# MPU-6050_BreakoutV11.net
KiCad netlist of a schematic drawn in EAGLE
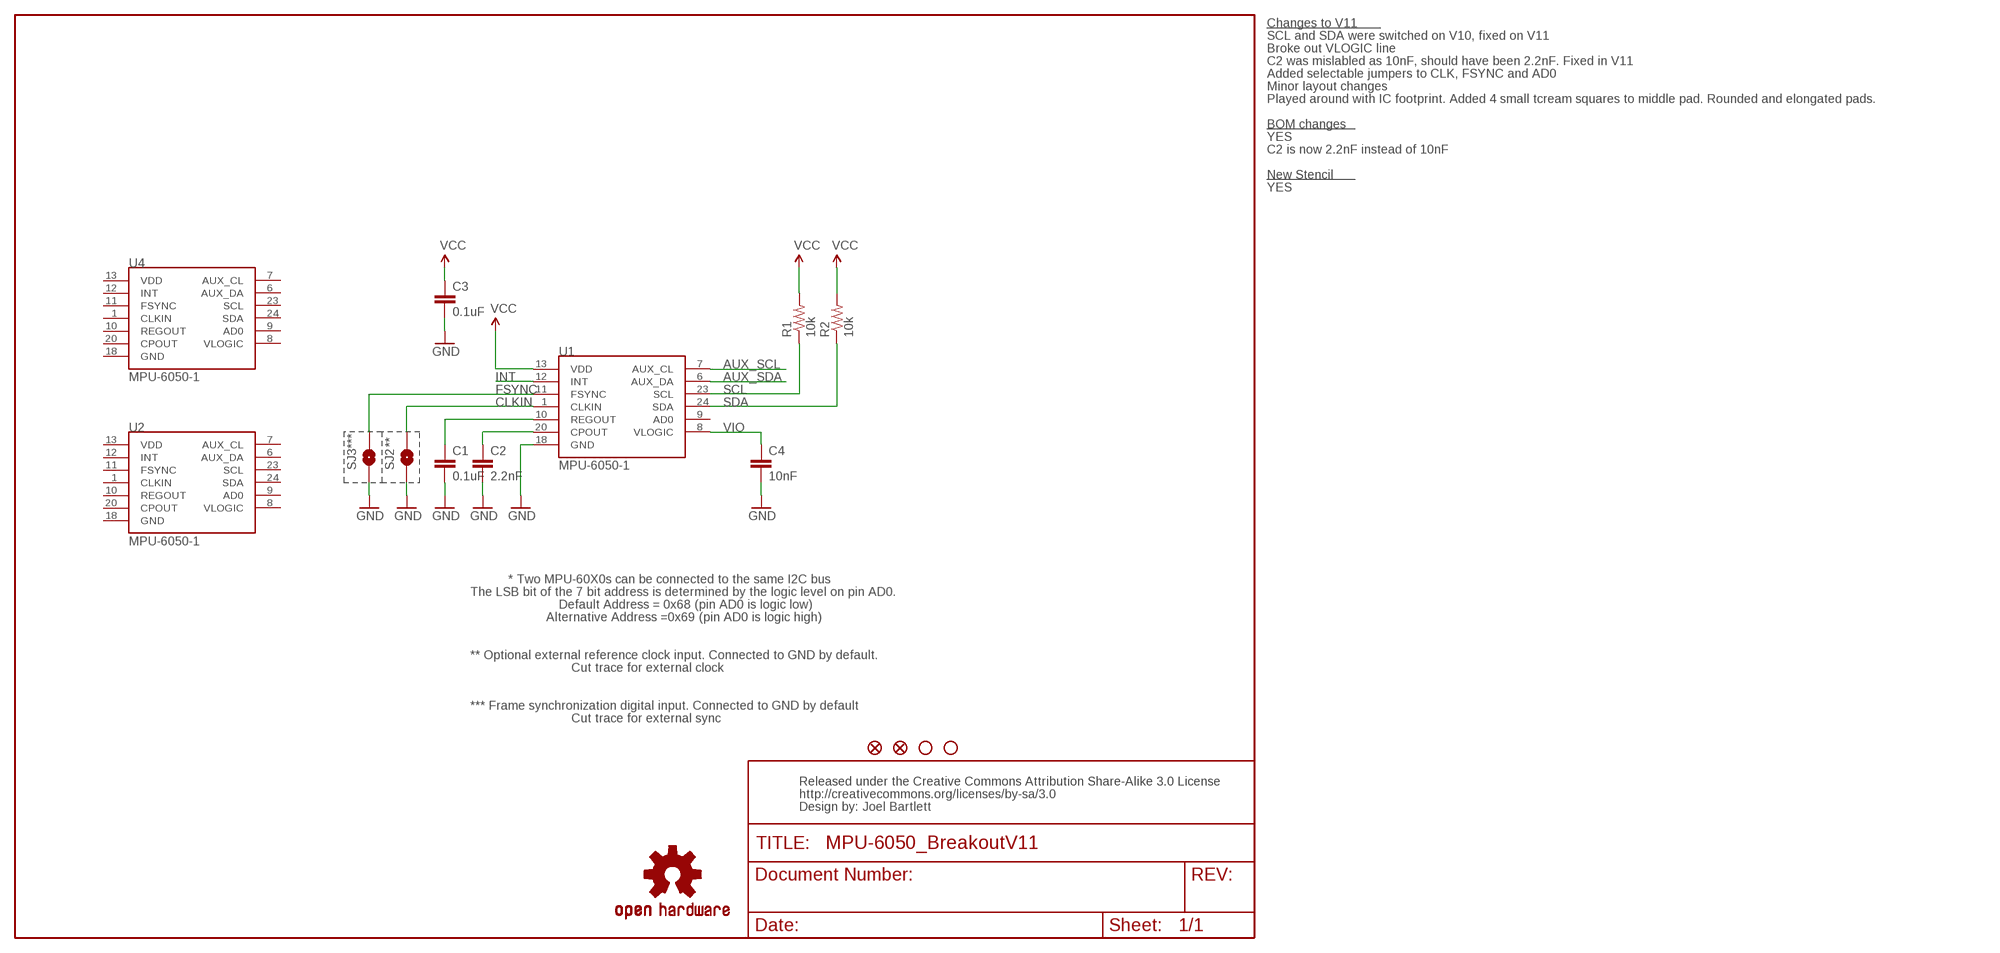
[diagram p0: schematic, sheet 1]

(export (version "E")
  (design (tool "Eeschema 10.0.6"))
  (components
    (comp (ref "C1")
      (value "0.1uF")
      (footprint "eagle-import:0402-CAP")
      (libsource (lib "eagle-import") (part "CAP0402-CAP"))
    )
    (comp (ref "C2")
      (value "2.2nF")
      (footprint "eagle-import:0402-CAP")
      (libsource (lib "eagle-import") (part "CAP0402-CAP"))
    )
    (comp (ref "C3")
      (value "0.1uF")
      (footprint "eagle-import:0402-CAP")
      (libsource (lib "eagle-import") (part "CAP0402-CAP"))
    )
    (comp (ref "C4")
      (value "10nF")
      (footprint "eagle-import:0402-CAP")
      (libsource (lib "eagle-import") (part "CAP0402-CAP"))
    )
    (comp (ref "JP2")
      (value "FIDUCIALUFIDUCIAL")
      (footprint "eagle-import:MICRO-FIDUCIAL")
      (libsource (lib "eagle-import") (part "FIDUCIALUFIDUCIAL"))
    )
    (comp (ref "JP3")
      (value "STAND-OFFTIGHT")
      (footprint "eagle-import:STAND-OFF-TIGHT")
      (libsource (lib "eagle-import") (part "STAND-OFFTIGHT"))
    )
    (comp (ref "JP4")
      (value "STAND-OFFTIGHT")
      (footprint "eagle-import:STAND-OFF-TIGHT")
      (libsource (lib "eagle-import") (part "STAND-OFFTIGHT"))
    )
    (comp (ref "JP5")
      (value "FIDUCIALUFIDUCIAL")
      (footprint "eagle-import:MICRO-FIDUCIAL")
      (libsource (lib "eagle-import") (part "FIDUCIALUFIDUCIAL"))
    )
    (comp (ref "R1")
      (value "10k")
      (footprint "eagle-import:0402-RES")
      (libsource (lib "eagle-import") (part "RESISTOR0402-RES"))
    )
    (comp (ref "R2")
      (value "10k")
      (footprint "eagle-import:0402-RES")
      (libsource (lib "eagle-import") (part "RESISTOR0402-RES"))
    )
    (comp (ref "SJ2")
      (value "SOLDERJUMPERTRACE")
      (footprint "eagle-import:SJ_2S-TRACE")
      (libsource (lib "eagle-import") (part "SOLDERJUMPERTRACE"))
    )
    (comp (ref "SJ3")
      (value "SOLDERJUMPERTRACE")
      (footprint "eagle-import:SJ_2S-TRACE")
      (libsource (lib "eagle-import") (part "SOLDERJUMPERTRACE"))
    )
    (comp (ref "U$1")
      (value "OSHW-LOGOS")
      (footprint "eagle-import:OSHW-LOGO-S")
      (libsource (lib "eagle-import") (part "OSHW-LOGOS"))
    )
    (comp (ref "U1")
      (value "MPU-6050-1")
      (footprint "eagle-import:QFN-24-4MM2")
      (libsource (lib "eagle-import") (part "MPU-6050-1"))
    )
    (comp (ref "U2")
      (value "MPU-6050-1")
      (footprint "eagle-import:QFN-24-4MM2")
      (libsource (lib "eagle-import") (part "MPU-6050-1"))
    )
    (comp (ref "U3")
      (value "CREATIVE_COMMONS")
      (footprint "eagle-import:CREATIVE_COMMONS")
      (libsource (lib "eagle-import") (part "CREATIVE_COMMONS"))
    )
    (comp (ref "U4")
      (value "MPU-6050-1")
      (footprint "eagle-import:QFN-24-4MM2")
      (libsource (lib "eagle-import") (part "MPU-6050-1"))
    )
  )
  (nets
    (net (code "1") (name "/AUX_SCL") (class "Default")
      (node (ref "U1") (pin "7") (pinfunction "AUX_CL_7") (pintype "bidirectional"))
    )
    (net (code "2") (name "/AUX_SDA") (class "Default")
      (node (ref "U1") (pin "6") (pinfunction "AUX_DA_6") (pintype "bidirectional"))
    )
    (net (code "3") (name "/CLKIN") (class "Default")
      (node (ref "SJ2") (pin "2") (pinfunction "2_2") (pintype "passive"))
      (node (ref "U1") (pin "1") (pinfunction "CLKIN_1") (pintype "bidirectional"))
    )
    (net (code "4") (name "/FSYNC") (class "Default")
      (node (ref "SJ3") (pin "2") (pinfunction "2_2") (pintype "passive"))
      (node (ref "U1") (pin "11") (pinfunction "FSYNC_11") (pintype "bidirectional"))
    )
    (net (code "5") (name "/INT") (class "Default")
      (node (ref "U1") (pin "12") (pinfunction "INT_12") (pintype "bidirectional"))
    )
    (net (code "6") (name "/SCL") (class "Default")
      (node (ref "R1") (pin "1") (pinfunction "1_1") (pintype "passive"))
      (node (ref "U1") (pin "23") (pinfunction "SCL_23") (pintype "bidirectional"))
    )
    (net (code "7") (name "/SDA") (class "Default")
      (node (ref "R2") (pin "1") (pinfunction "1_1") (pintype "passive"))
      (node (ref "U1") (pin "24") (pinfunction "SDA_24") (pintype "bidirectional"))
    )
    (net (code "8") (name "/VIO") (class "Default")
      (node (ref "C4") (pin "1") (pinfunction "1_1") (pintype "passive"))
      (node (ref "U1") (pin "8") (pinfunction "VLOGIC_8") (pintype "bidirectional"))
    )
    (net (code "9") (name "GND") (class "Default")
      (node (ref "C1") (pin "2") (pinfunction "2_2") (pintype "passive"))
      (node (ref "C2") (pin "2") (pinfunction "2_2") (pintype "passive"))
      (node (ref "C3") (pin "2") (pinfunction "2_2") (pintype "passive"))
      (node (ref "C4") (pin "2") (pinfunction "2_2") (pintype "passive"))
      (node (ref "SJ2") (pin "1") (pinfunction "1_1") (pintype "passive"))
      (node (ref "SJ3") (pin "1") (pinfunction "1_1") (pintype "passive"))
      (node (ref "U1") (pin "18") (pinfunction "GND_18") (pintype "bidirectional"))
    )
    (net (code "10") (name "Net-(U1-CPOUT)") (class "Default")
      (node (ref "C2") (pin "1") (pinfunction "1_1") (pintype "passive"))
      (node (ref "U1") (pin "20") (pinfunction "CPOUT_20") (pintype "bidirectional"))
    )
    (net (code "11") (name "Net-(U1-REGOUT)") (class "Default")
      (node (ref "C1") (pin "1") (pinfunction "1_1") (pintype "passive"))
      (node (ref "U1") (pin "10") (pinfunction "REGOUT_10") (pintype "bidirectional"))
    )
    (net (code "12") (name "VCC") (class "Default")
      (node (ref "C3") (pin "1") (pinfunction "1_1") (pintype "passive"))
      (node (ref "R1") (pin "2") (pinfunction "2_2") (pintype "passive"))
      (node (ref "R2") (pin "2") (pinfunction "2_2") (pintype "passive"))
      (node (ref "U1") (pin "13") (pinfunction "VDD_13") (pintype "bidirectional"))
    )
    (net (code "13") (name "unconnected-(U1-AD0-Pad9)") (class "Default")
      (node (ref "U1") (pin "9") (pinfunction "AD0_9") (pintype "bidirectional"))
    )
    (net (code "14") (name "unconnected-(U2-AD0-Pad9)") (class "Default")
      (node (ref "U2") (pin "9") (pinfunction "AD0_9") (pintype "bidirectional"))
    )
    (net (code "15") (name "unconnected-(U2-AUX_CL-Pad7)") (class "Default")
      (node (ref "U2") (pin "7") (pinfunction "AUX_CL_7") (pintype "bidirectional"))
    )
    (net (code "16") (name "unconnected-(U2-AUX_DA-Pad6)") (class "Default")
      (node (ref "U2") (pin "6") (pinfunction "AUX_DA_6") (pintype "bidirectional"))
    )
    (net (code "17") (name "unconnected-(U2-CLKIN-Pad1)") (class "Default")
      (node (ref "U2") (pin "1") (pinfunction "CLKIN_1") (pintype "bidirectional"))
    )
    (net (code "18") (name "unconnected-(U2-CPOUT-Pad20)") (class "Default")
      (node (ref "U2") (pin "20") (pinfunction "CPOUT_20") (pintype "bidirectional"))
    )
    (net (code "19") (name "unconnected-(U2-FSYNC-Pad11)") (class "Default")
      (node (ref "U2") (pin "11") (pinfunction "FSYNC_11") (pintype "bidirectional"))
    )
    (net (code "20") (name "unconnected-(U2-GND-Pad18)") (class "Default")
      (node (ref "U2") (pin "18") (pinfunction "GND_18") (pintype "bidirectional"))
    )
    (net (code "21") (name "unconnected-(U2-INT-Pad12)") (class "Default")
      (node (ref "U2") (pin "12") (pinfunction "INT_12") (pintype "bidirectional"))
    )
    (net (code "22") (name "unconnected-(U2-REGOUT-Pad10)") (class "Default")
      (node (ref "U2") (pin "10") (pinfunction "REGOUT_10") (pintype "bidirectional"))
    )
    (net (code "23") (name "unconnected-(U2-SCL-Pad23)") (class "Default")
      (node (ref "U2") (pin "23") (pinfunction "SCL_23") (pintype "bidirectional"))
    )
    (net (code "24") (name "unconnected-(U2-SDA-Pad24)") (class "Default")
      (node (ref "U2") (pin "24") (pinfunction "SDA_24") (pintype "bidirectional"))
    )
    (net (code "25") (name "unconnected-(U2-VDD-Pad13)") (class "Default")
      (node (ref "U2") (pin "13") (pinfunction "VDD_13") (pintype "bidirectional"))
    )
    (net (code "26") (name "unconnected-(U2-VLOGIC-Pad8)") (class "Default")
      (node (ref "U2") (pin "8") (pinfunction "VLOGIC_8") (pintype "bidirectional"))
    )
    (net (code "27") (name "unconnected-(U4-AD0-Pad9)") (class "Default")
      (node (ref "U4") (pin "9") (pinfunction "AD0_9") (pintype "bidirectional"))
    )
    (net (code "28") (name "unconnected-(U4-AUX_CL-Pad7)") (class "Default")
      (node (ref "U4") (pin "7") (pinfunction "AUX_CL_7") (pintype "bidirectional"))
    )
    (net (code "29") (name "unconnected-(U4-AUX_DA-Pad6)") (class "Default")
      (node (ref "U4") (pin "6") (pinfunction "AUX_DA_6") (pintype "bidirectional"))
    )
    (net (code "30") (name "unconnected-(U4-CLKIN-Pad1)") (class "Default")
      (node (ref "U4") (pin "1") (pinfunction "CLKIN_1") (pintype "bidirectional"))
    )
    (net (code "31") (name "unconnected-(U4-CPOUT-Pad20)") (class "Default")
      (node (ref "U4") (pin "20") (pinfunction "CPOUT_20") (pintype "bidirectional"))
    )
    (net (code "32") (name "unconnected-(U4-FSYNC-Pad11)") (class "Default")
      (node (ref "U4") (pin "11") (pinfunction "FSYNC_11") (pintype "bidirectional"))
    )
    (net (code "33") (name "unconnected-(U4-GND-Pad18)") (class "Default")
      (node (ref "U4") (pin "18") (pinfunction "GND_18") (pintype "bidirectional"))
    )
    (net (code "34") (name "unconnected-(U4-INT-Pad12)") (class "Default")
      (node (ref "U4") (pin "12") (pinfunction "INT_12") (pintype "bidirectional"))
    )
    (net (code "35") (name "unconnected-(U4-REGOUT-Pad10)") (class "Default")
      (node (ref "U4") (pin "10") (pinfunction "REGOUT_10") (pintype "bidirectional"))
    )
    (net (code "36") (name "unconnected-(U4-SCL-Pad23)") (class "Default")
      (node (ref "U4") (pin "23") (pinfunction "SCL_23") (pintype "bidirectional"))
    )
    (net (code "37") (name "unconnected-(U4-SDA-Pad24)") (class "Default")
      (node (ref "U4") (pin "24") (pinfunction "SDA_24") (pintype "bidirectional"))
    )
    (net (code "38") (name "unconnected-(U4-VDD-Pad13)") (class "Default")
      (node (ref "U4") (pin "13") (pinfunction "VDD_13") (pintype "bidirectional"))
    )
    (net (code "39") (name "unconnected-(U4-VLOGIC-Pad8)") (class "Default")
      (node (ref "U4") (pin "8") (pinfunction "VLOGIC_8") (pintype "bidirectional"))
    )
  )
)
